# IM920sL_module.net
KiCad netlist of a schematic drawn in EAGLE
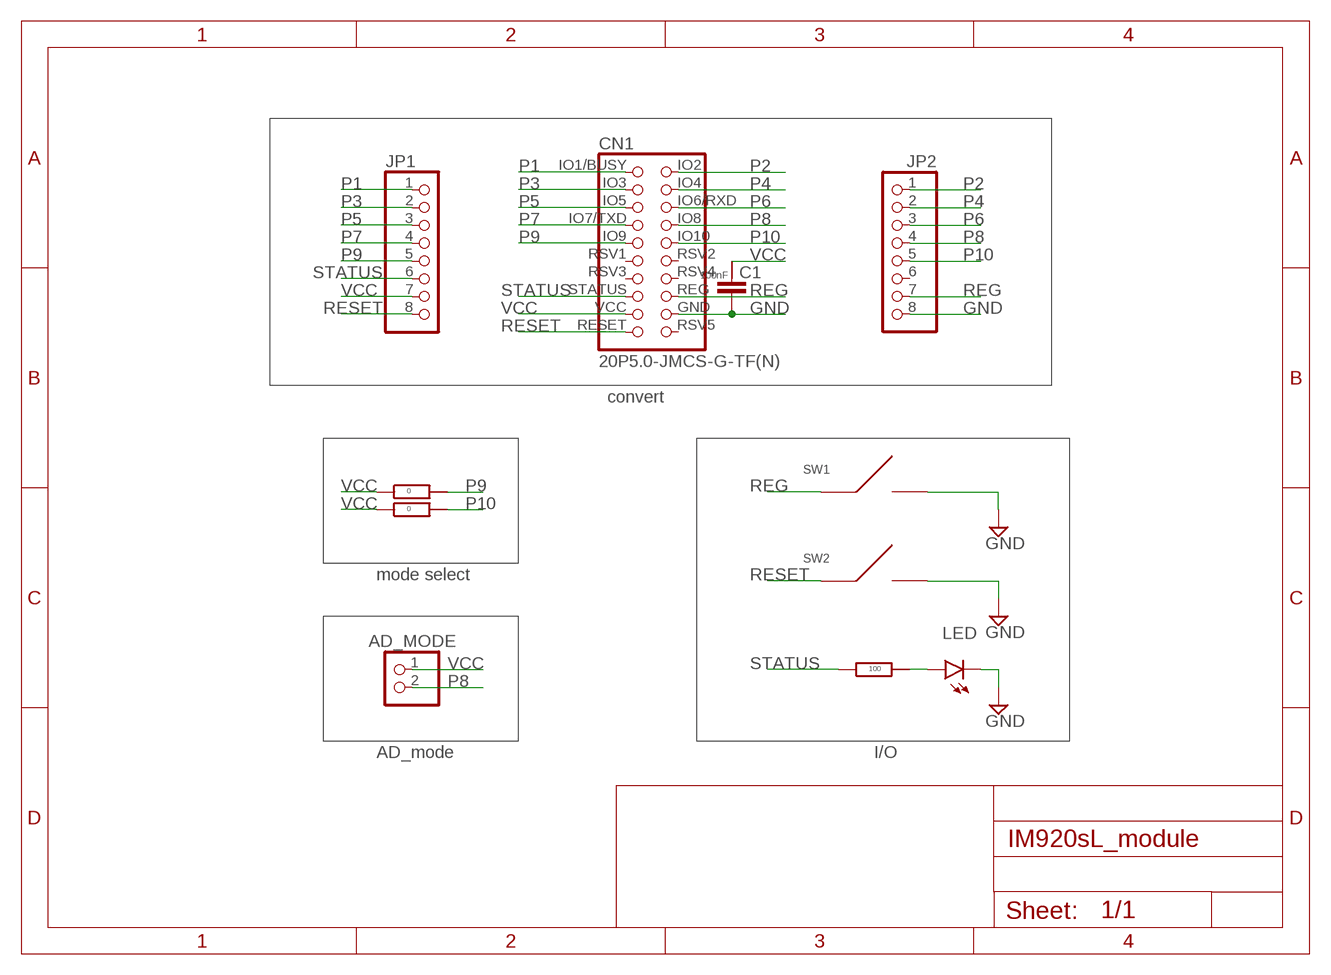
[diagram p0: schematic, sheet 1]

(export (version "E")
  (design (tool "Eeschema 10.0.6"))
  (components
    (comp (ref "AD_MODE")
      (value "PINHD-1X2")
      (footprint "eagle-import:1X02")
      (libsource (lib "eagle-import") (part "PINHD-1X2"))
    )
    (comp (ref "C1")
      (value "GCM188L81H104KA57")
      (footprint "eagle-import:GCM188L81H104KA57")
      (libsource (lib "eagle-import") (part "GCM188L81H104KA57"))
    )
    (comp (ref "CN1")
      (value "20P5.0-JMCS-G-TF(N)")
      (footprint "eagle-import:20P5.0-JMCS-G-TF(N)")
      (libsource (lib "eagle-import") (part "20P5.0-JMCS-G-TF(N)"))
    )
    (comp (ref "JP1")
      (value "PINHD-1X8")
      (footprint "eagle-import:1X08")
      (libsource (lib "eagle-import") (part "PINHD-1X8"))
    )
    (comp (ref "JP2")
      (value "PINHD-1X8")
      (footprint "eagle-import:1X08")
      (libsource (lib "eagle-import") (part "PINHD-1X8"))
    )
    (comp (ref "LED")
      (value "SML-E12V8WT86")
      (footprint "eagle-import:SML-E12V8WT86")
      (libsource (lib "eagle-import") (part "SML-E12V8WT86"))
    )
    (comp (ref "R1")
      (value "RG2012N-101-B-T5")
      (footprint "eagle-import:RG2012")
      (libsource (lib "eagle-import") (part "RG2012N-101-B-T5"))
    )
    (comp (ref "R2")
      (value "RG2012-0Ω")
      (footprint "eagle-import:RG2012")
      (libsource (lib "eagle-import") (part "RG2012-0Ω"))
    )
    (comp (ref "R3")
      (value "RG2012-0Ω")
      (footprint "eagle-import:RG2012")
      (libsource (lib "eagle-import") (part "RG2012-0Ω"))
    )
    (comp (ref "SW1")
      (value "一般的なタクトスイッチ")
      (footprint "eagle-import:一般的なタクトスイッチ")
      (libsource (lib "eagle-import") (part "一般的なタクトスイッチ"))
    )
    (comp (ref "SW2")
      (value "一般的なタクトスイッチ")
      (footprint "eagle-import:一般的なタクトスイッチ")
      (libsource (lib "eagle-import") (part "一般的なタクトスイッチ"))
    )
  )
  (nets
    (net (code "1") (name "/P1") (class "Default")
      (node (ref "CN1") (pin "IO1/BUSY") (pinfunction "IO1/BUSY_IO1/BUSY") (pintype "passive"))
      (node (ref "JP1") (pin "1") (pinfunction "1_1") (pintype "passive"))
    )
    (net (code "2") (name "/P2") (class "Default")
      (node (ref "CN1") (pin "IO2") (pinfunction "IO2_IO2") (pintype "passive"))
      (node (ref "JP2") (pin "1") (pinfunction "1_1") (pintype "passive"))
    )
    (net (code "3") (name "/P3") (class "Default")
      (node (ref "CN1") (pin "IO3") (pinfunction "IO3_IO3") (pintype "passive"))
      (node (ref "JP1") (pin "2") (pinfunction "2_2") (pintype "passive"))
    )
    (net (code "4") (name "/P4") (class "Default")
      (node (ref "CN1") (pin "IO4") (pinfunction "IO4_IO4") (pintype "passive"))
      (node (ref "JP2") (pin "2") (pinfunction "2_2") (pintype "passive"))
    )
    (net (code "5") (name "/P5") (class "Default")
      (node (ref "CN1") (pin "IO5") (pinfunction "IO5_IO5") (pintype "passive"))
      (node (ref "JP1") (pin "3") (pinfunction "3_3") (pintype "passive"))
    )
    (net (code "6") (name "/P6") (class "Default")
      (node (ref "CN1") (pin "IO6/RXD") (pinfunction "IO6/RXD_IO6/RXD") (pintype "passive"))
      (node (ref "JP2") (pin "3") (pinfunction "3_3") (pintype "passive"))
    )
    (net (code "7") (name "/P7") (class "Default")
      (node (ref "CN1") (pin "IO7/TXD") (pinfunction "IO7/TXD_IO7/TXD") (pintype "passive"))
      (node (ref "JP1") (pin "4") (pinfunction "4_4") (pintype "passive"))
    )
    (net (code "8") (name "/P8") (class "Default")
      (node (ref "AD_MODE") (pin "2") (pinfunction "2_2") (pintype "passive"))
      (node (ref "CN1") (pin "IO8") (pinfunction "IO8_IO8") (pintype "passive"))
      (node (ref "JP2") (pin "4") (pinfunction "4_4") (pintype "passive"))
    )
    (net (code "9") (name "/P9") (class "Default")
      (node (ref "CN1") (pin "IO9") (pinfunction "IO9_IO9") (pintype "passive"))
      (node (ref "JP1") (pin "5") (pinfunction "5_5") (pintype "passive"))
      (node (ref "R2") (pin "LEFT") (pinfunction "P$1_LEFT") (pintype "bidirectional"))
    )
    (net (code "10") (name "/P10") (class "Default")
      (node (ref "CN1") (pin "IO10") (pinfunction "IO10_IO10") (pintype "passive"))
      (node (ref "JP2") (pin "5") (pinfunction "5_5") (pintype "passive"))
      (node (ref "R3") (pin "LEFT") (pinfunction "P$1_LEFT") (pintype "bidirectional"))
    )
    (net (code "11") (name "/REG") (class "Default")
      (node (ref "CN1") (pin "REG") (pinfunction "REG_REG") (pintype "passive"))
      (node (ref "JP2") (pin "7") (pinfunction "7_7") (pintype "passive"))
      (node (ref "SW1") (pin "T4") (pinfunction "P$2_T4") (pintype "bidirectional"))
    )
    (net (code "12") (name "/RESET") (class "Default")
      (node (ref "CN1") (pin "RESET") (pinfunction "RESET_RESET") (pintype "passive"))
      (node (ref "JP1") (pin "8") (pinfunction "8_8") (pintype "passive"))
      (node (ref "SW2") (pin "T4") (pinfunction "P$2_T4") (pintype "bidirectional"))
    )
    (net (code "13") (name "/STATUS") (class "Default")
      (node (ref "CN1") (pin "STATUS") (pinfunction "STATUS_STATUS") (pintype "passive"))
      (node (ref "JP1") (pin "6") (pinfunction "6_6") (pintype "passive"))
      (node (ref "R1") (pin "RIGHT") (pinfunction "P$2_RIGHT") (pintype "bidirectional"))
    )
    (net (code "14") (name "/VCC") (class "Default")
      (node (ref "AD_MODE") (pin "1") (pinfunction "1_1") (pintype "passive"))
      (node (ref "C1") (pin "P$1") (pinfunction "P$1_P$1") (pintype "bidirectional"))
      (node (ref "CN1") (pin "VCC") (pinfunction "VCC_VCC") (pintype "passive"))
      (node (ref "JP1") (pin "7") (pinfunction "7_7") (pintype "passive"))
      (node (ref "R2") (pin "RIGHT") (pinfunction "P$2_RIGHT") (pintype "bidirectional"))
      (node (ref "R3") (pin "RIGHT") (pinfunction "P$2_RIGHT") (pintype "bidirectional"))
    )
    (net (code "15") (name "GND") (class "Default")
      (node (ref "C1") (pin "P$2") (pinfunction "P$2_P$2") (pintype "bidirectional"))
      (node (ref "CN1") (pin "GND") (pinfunction "GND_GND") (pintype "passive"))
      (node (ref "JP2") (pin "8") (pinfunction "8_8") (pintype "passive"))
      (node (ref "LED") (pin "K") (pinfunction "C_K") (pintype "passive"))
      (node (ref "SW1") (pin "T2") (pinfunction "P$1_T2") (pintype "bidirectional"))
      (node (ref "SW2") (pin "T2") (pinfunction "P$1_T2") (pintype "bidirectional"))
    )
    (net (code "16") (name "Net-(R1-P$1)") (class "Default")
      (node (ref "LED") (pin "A") (pinfunction "A_A") (pintype "passive"))
      (node (ref "R1") (pin "LEFT") (pinfunction "P$1_LEFT") (pintype "bidirectional"))
    )
    (net (code "17") (name "unconnected-(CN1-PadRSV1)") (class "Default")
      (node (ref "CN1") (pin "RSV1") (pinfunction "RSV1_RSV1") (pintype "passive"))
    )
    (net (code "18") (name "unconnected-(CN1-PadRSV2)") (class "Default")
      (node (ref "CN1") (pin "RSV2") (pinfunction "RSV2_RSV2") (pintype "passive"))
    )
    (net (code "19") (name "unconnected-(CN1-PadRSV3)") (class "Default")
      (node (ref "CN1") (pin "RSV3") (pinfunction "RSV3_RSV3") (pintype "passive"))
    )
    (net (code "20") (name "unconnected-(CN1-PadRSV4)") (class "Default")
      (node (ref "CN1") (pin "RSV4") (pinfunction "RSV4_RSV4") (pintype "passive"))
    )
    (net (code "21") (name "unconnected-(CN1-PadRSV5)") (class "Default")
      (node (ref "CN1") (pin "RSV5") (pinfunction "RSV5_RSV5") (pintype "passive"))
    )
    (net (code "22") (name "unconnected-(JP2-Pad6)") (class "Default")
      (node (ref "JP2") (pin "6") (pinfunction "6_6") (pintype "passive"))
    )
  )
)
